# DP2MBPR_1_0.net
KiCad netlist of a schematic drawn in EAGLE
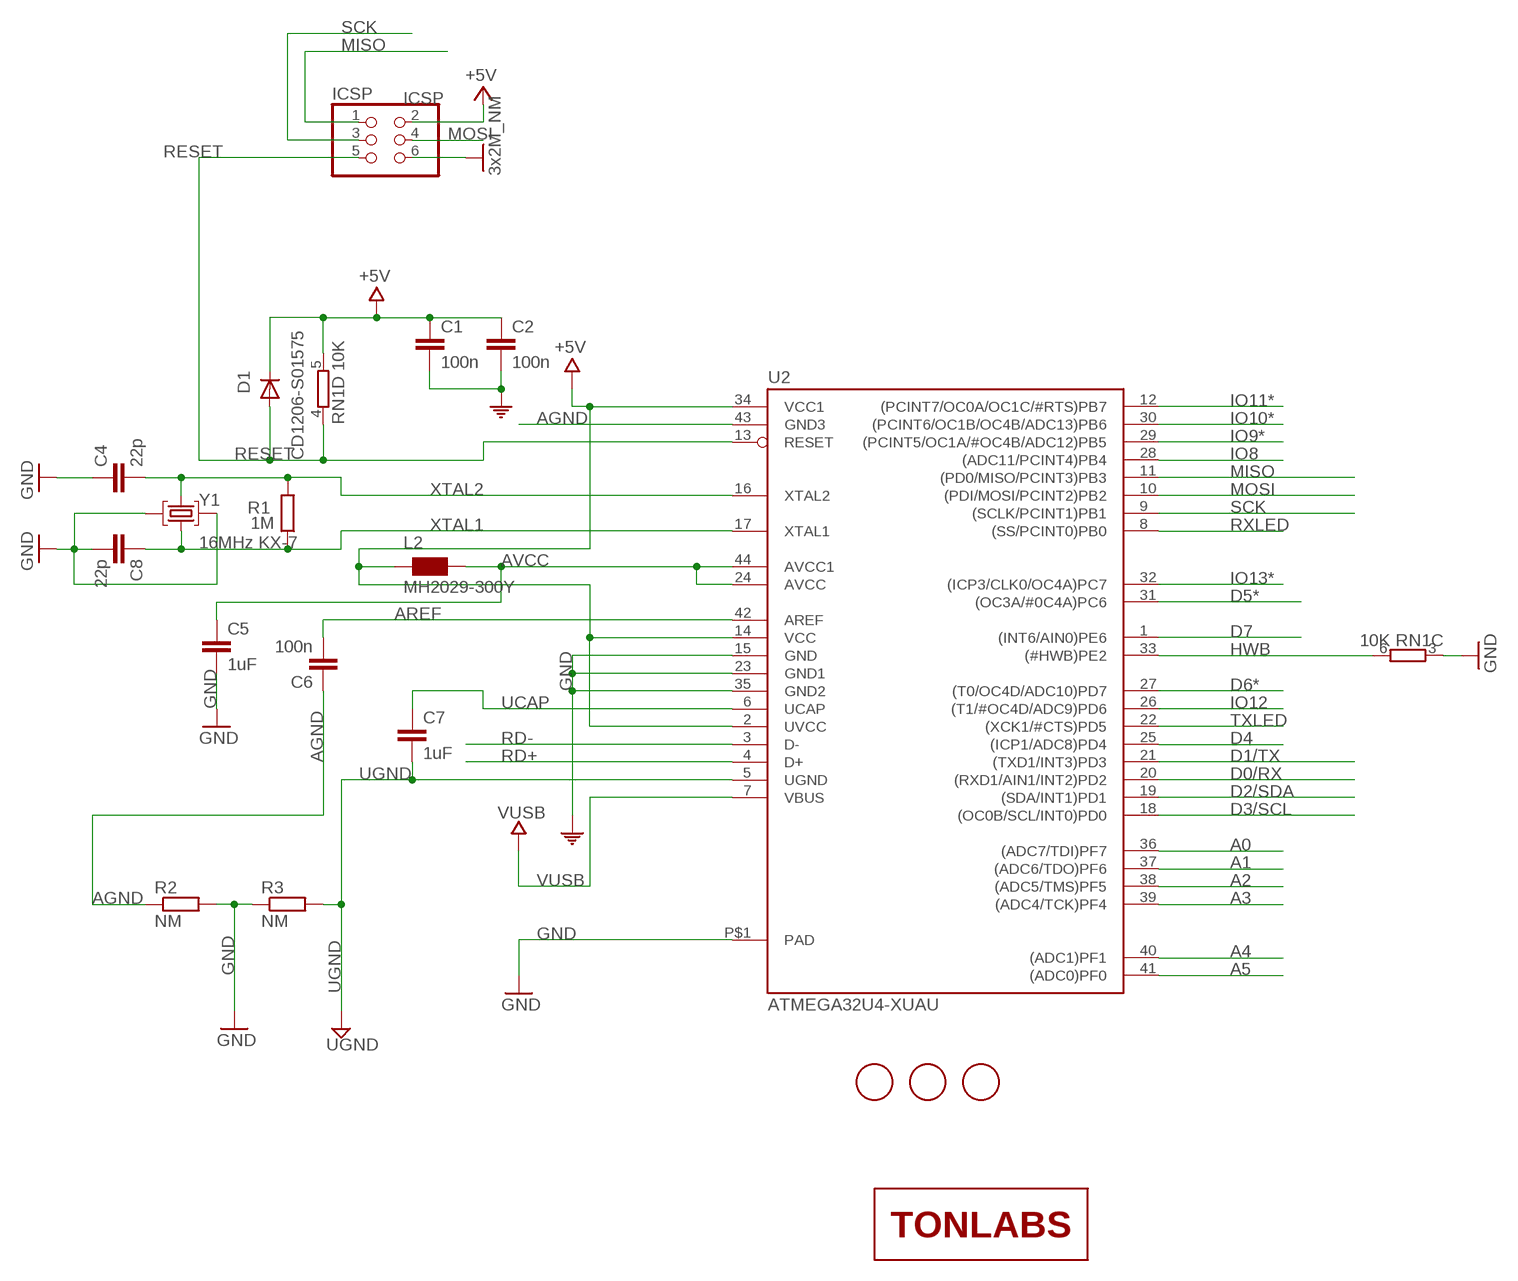
[diagram p0: schematic, sheet 2]
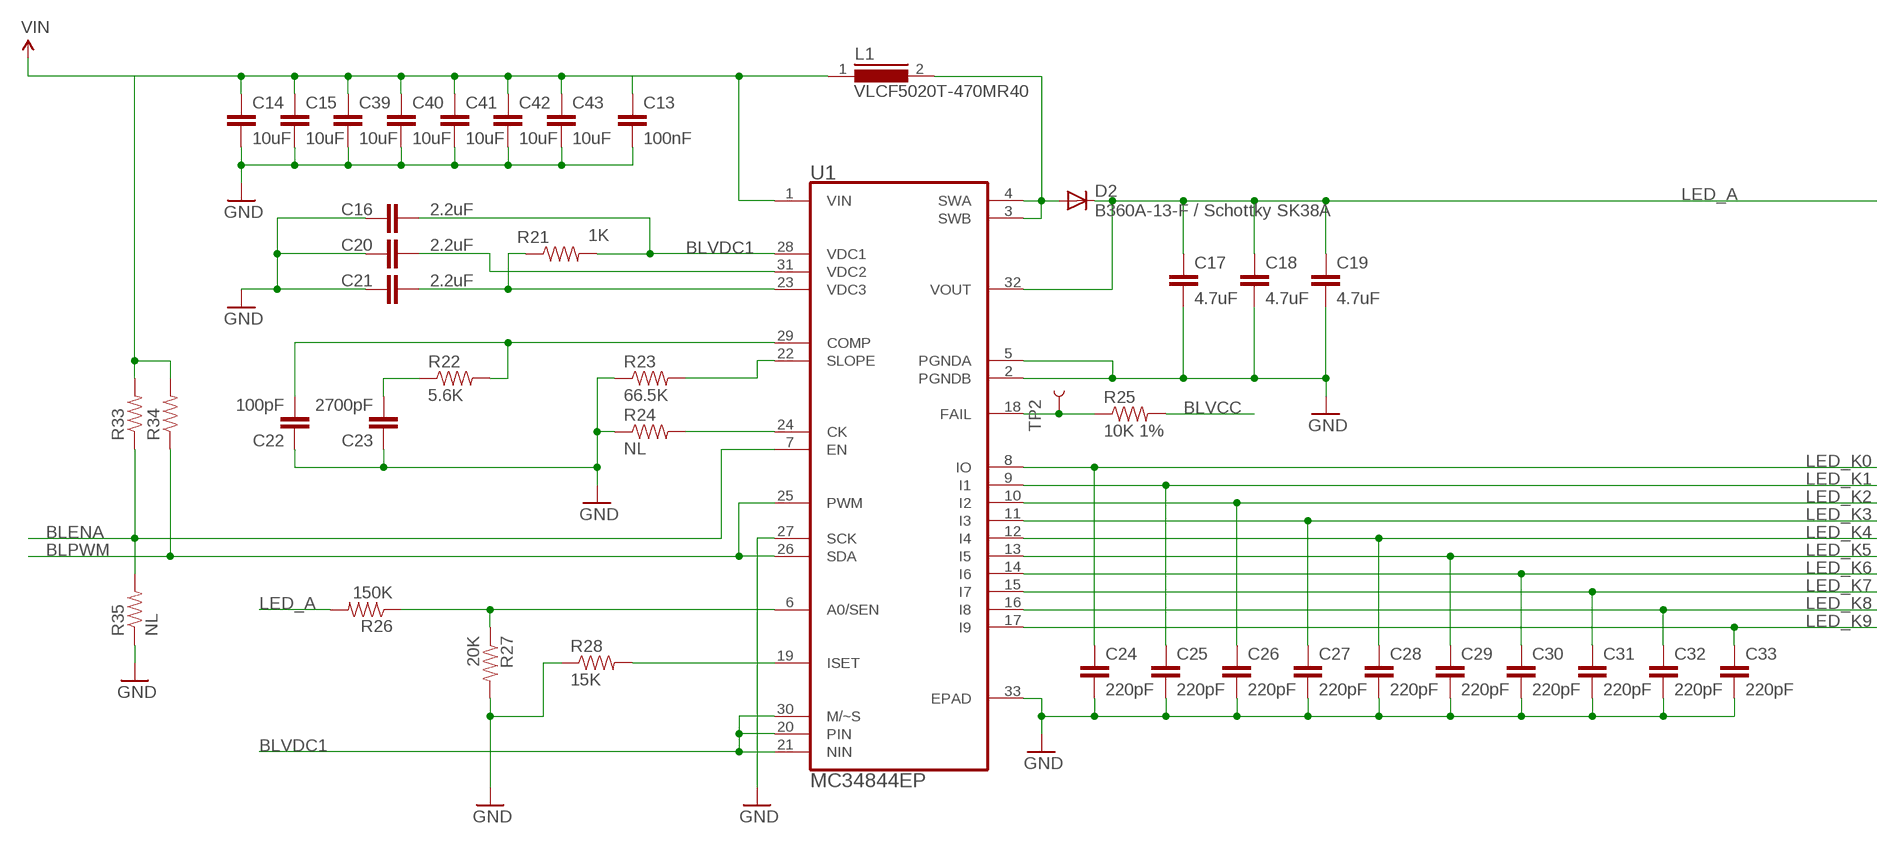
[diagram p1: schematic, sheet 3]
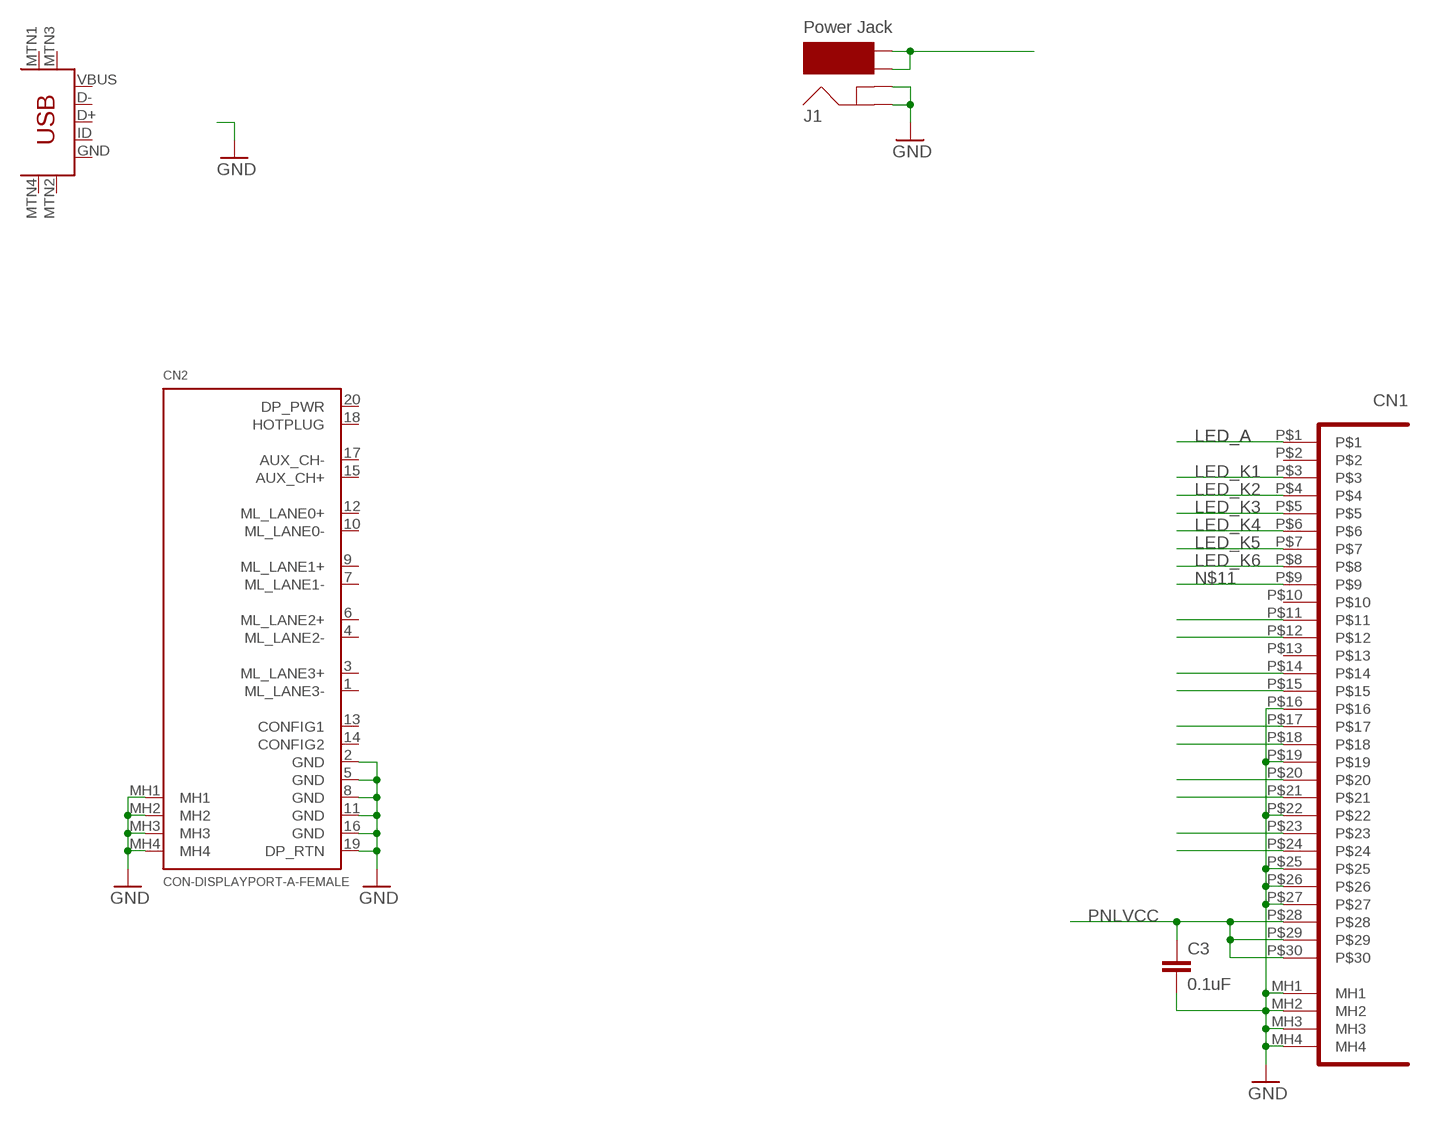
[diagram p2: schematic, sheet 4]

(export (version "E")
  (design (tool "Eeschema 10.0.6"))
  (components
    (comp (ref "C1")
      (value "100n")
      (footprint "eagle-import:C0603-ROUND")
      (libsource (lib "eagle-import") (part "C-EUC0603"))
    )
    (comp (ref "C2")
      (value "100n")
      (footprint "eagle-import:C0603-ROUND")
      (libsource (lib "eagle-import") (part "C-EUC0603"))
    )
    (comp (ref "C4")
      (value "22p")
      (footprint "eagle-import:C0603-ROUND")
      (libsource (lib "eagle-import") (part "C-EUC0603"))
    )
    (comp (ref "C5")
      (value "1uF")
      (footprint "eagle-import:C0603-ROUND")
      (libsource (lib "eagle-import") (part "C-EUC0603"))
    )
    (comp (ref "C6")
      (value "100n")
      (footprint "eagle-import:C0603-ROUND")
      (libsource (lib "eagle-import") (part "C-EUC0603"))
    )
    (comp (ref "C7")
      (value "1uF")
      (footprint "eagle-import:C0603-ROUND")
      (libsource (lib "eagle-import") (part "C-EUC0603"))
    )
    (comp (ref "C8")
      (value "22p")
      (footprint "eagle-import:C0603-ROUND")
      (libsource (lib "eagle-import") (part "C-EUC0603"))
    )
    (comp (ref "D1")
      (value "CD1206-S01575")
      (footprint "eagle-import:MINIMELF")
      (libsource (lib "eagle-import") (part "DIODE-MINIMELF"))
    )
    (comp (ref "FID1")
      (value "FIDUCIALMOUNT")
      (footprint "eagle-import:FIDUCIA-MOUNT")
      (libsource (lib "eagle-import") (part "FIDUCIALMOUNT"))
    )
    (comp (ref "FID2")
      (value "FIDUCIALMOUNT")
      (footprint "eagle-import:FIDUCIA-MOUNT")
      (libsource (lib "eagle-import") (part "FIDUCIALMOUNT"))
    )
    (comp (ref "FID3")
      (value "FIDUCIALMOUNT")
      (footprint "eagle-import:FIDUCIA-MOUNT")
      (libsource (lib "eagle-import") (part "FIDUCIALMOUNT"))
    )
    (comp (ref "ICSP")
      (value "ICSP")
      (footprint "eagle-import:2X03")
      (libsource (lib "eagle-import") (part "PINHD-2X3"))
    )
    (comp (ref "L2")
      (value "MH2029-300Y")
      (footprint "eagle-import:0805")
      (libsource (lib "eagle-import") (part "WE-CBF_0805"))
    )
    (comp (ref "LOGO1")
      (value "LOGO-TONYLABSMED-LANDSCAPE")
      (footprint "eagle-import:LOGO-TONYLABS-MED-LANDSCAPE")
      (libsource (lib "eagle-import") (part "LOGO-TONYLABSMED-LANDSCAPE"))
    )
    (comp (ref "R1")
      (value "1M")
      (footprint "eagle-import:R0603-ROUND")
      (libsource (lib "eagle-import") (part "R-EU_R0603"))
    )
    (comp (ref "R2")
      (value "NM")
      (footprint "eagle-import:R0402")
      (libsource (lib "eagle-import") (part "R-EU_R0402"))
    )
    (comp (ref "R3")
      (value "NM")
      (footprint "eagle-import:R0402")
      (libsource (lib "eagle-import") (part "R-EU_R0402"))
    )
    (comp (ref "RN1")
      (value "10K")
      (footprint "eagle-import:CAY16")
      (libsource (lib "eagle-import") (part "4R-NCAY16"))
    )
    (comp (ref "U2")
      (value "ATMEGA32U4-XUAU")
      (footprint "eagle-import:TQFP44-PAD")
      (libsource (lib "eagle-import") (part "ATMEGA32U4-XUAU"))
    )
    (comp (ref "Y1")
      (value "16MHz KX-7")
      (footprint "eagle-import:CRYSTAL-3.2-2.5")
      (libsource (lib "eagle-import") (part "CRYSTAL-3.2-2.5"))
    )
    (comp (ref "C13")
      (value "100nF")
      (footprint "eagle-import:0805")
      (libsource (lib "eagle-import") (part "CAP0805"))
    )
    (comp (ref "C14")
      (value "10uF")
      (footprint "eagle-import:0805")
      (libsource (lib "eagle-import") (part "CAP0805"))
    )
    (comp (ref "C15")
      (value "10uF")
      (footprint "eagle-import:0805")
      (libsource (lib "eagle-import") (part "CAP0805"))
    )
    (comp (ref "C16")
      (value "2.2uF")
      (footprint "eagle-import:0805")
      (libsource (lib "eagle-import") (part "CAP0805"))
    )
    (comp (ref "C17")
      (value "4.7uF")
      (footprint "eagle-import:1210")
      (libsource (lib "eagle-import") (part "CAP1210"))
    )
    (comp (ref "C18")
      (value "4.7uF")
      (footprint "eagle-import:1210")
      (libsource (lib "eagle-import") (part "CAP1210"))
    )
    (comp (ref "C19")
      (value "4.7uF")
      (footprint "eagle-import:1210")
      (libsource (lib "eagle-import") (part "CAP1210"))
    )
    (comp (ref "C20")
      (value "2.2uF")
      (footprint "eagle-import:0805")
      (libsource (lib "eagle-import") (part "CAP0805"))
    )
    (comp (ref "C21")
      (value "2.2uF")
      (footprint "eagle-import:0805")
      (libsource (lib "eagle-import") (part "CAP0805"))
    )
    (comp (ref "C22")
      (value "100pF")
      (footprint "eagle-import:0805")
      (libsource (lib "eagle-import") (part "CAP0805"))
    )
    (comp (ref "C23")
      (value "2700pF")
      (footprint "eagle-import:0805")
      (libsource (lib "eagle-import") (part "CAP0805"))
    )
    (comp (ref "C24")
      (value "220pF")
      (footprint "eagle-import:0603-CAP")
      (libsource (lib "eagle-import") (part "CAP0603-CAP"))
    )
    (comp (ref "C25")
      (value "220pF")
      (footprint "eagle-import:0603-CAP")
      (libsource (lib "eagle-import") (part "CAP0603-CAP"))
    )
    (comp (ref "C26")
      (value "220pF")
      (footprint "eagle-import:0603-CAP")
      (libsource (lib "eagle-import") (part "CAP0603-CAP"))
    )
    (comp (ref "C27")
      (value "220pF")
      (footprint "eagle-import:0603-CAP")
      (libsource (lib "eagle-import") (part "CAP0603-CAP"))
    )
    (comp (ref "C28")
      (value "220pF")
      (footprint "eagle-import:0603-CAP")
      (libsource (lib "eagle-import") (part "CAP0603-CAP"))
    )
    (comp (ref "C29")
      (value "220pF")
      (footprint "eagle-import:0603-CAP")
      (libsource (lib "eagle-import") (part "CAP0603-CAP"))
    )
    (comp (ref "C30")
      (value "220pF")
      (footprint "eagle-import:0603-CAP")
      (libsource (lib "eagle-import") (part "CAP0603-CAP"))
    )
    (comp (ref "C31")
      (value "220pF")
      (footprint "eagle-import:0603-CAP")
      (libsource (lib "eagle-import") (part "CAP0603-CAP"))
    )
    (comp (ref "C32")
      (value "220pF")
      (footprint "eagle-import:0603-CAP")
      (libsource (lib "eagle-import") (part "CAP0603-CAP"))
    )
    (comp (ref "C33")
      (value "220pF")
      (footprint "eagle-import:0603-CAP")
      (libsource (lib "eagle-import") (part "CAP0603-CAP"))
    )
    (comp (ref "C39")
      (value "10uF")
      (footprint "eagle-import:0805")
      (libsource (lib "eagle-import") (part "CAP0805"))
    )
    (comp (ref "C40")
      (value "10uF")
      (footprint "eagle-import:0805")
      (libsource (lib "eagle-import") (part "CAP0805"))
    )
    (comp (ref "C41")
      (value "10uF")
      (footprint "eagle-import:0805")
      (libsource (lib "eagle-import") (part "CAP0805"))
    )
    (comp (ref "C42")
      (value "10uF")
      (footprint "eagle-import:0805")
      (libsource (lib "eagle-import") (part "CAP0805"))
    )
    (comp (ref "C43")
      (value "10uF")
      (footprint "eagle-import:0805")
      (libsource (lib "eagle-import") (part "CAP0805"))
    )
    (comp (ref "D2")
      (value "B360A-13-F / Schottky SK38A")
      (footprint "eagle-import:SMB")
      (libsource (lib "eagle-import") (part "DIODE-SMB"))
    )
    (comp (ref "L1")
      (value "VLCF5020T-470MR40")
      (footprint "eagle-import:SLF7045")
      (libsource (lib "eagle-import") (part "SLF7045"))
    )
    (comp (ref "R21")
      (value "1K")
      (footprint "eagle-import:0603-RES")
      (libsource (lib "eagle-import") (part "RESISTOR0603-RES"))
    )
    (comp (ref "R22")
      (value "5.6K")
      (footprint "eagle-import:0603-RES")
      (libsource (lib "eagle-import") (part "RESISTOR0603-RES"))
    )
    (comp (ref "R23")
      (value "66.5K")
      (footprint "eagle-import:0603-RES")
      (libsource (lib "eagle-import") (part "RESISTOR0603-RES"))
    )
    (comp (ref "R24")
      (value "NL")
      (footprint "eagle-import:0603-RES")
      (libsource (lib "eagle-import") (part "RESISTOR0603-RES"))
    )
    (comp (ref "R25")
      (value "10K 1%")
      (footprint "eagle-import:0603-RES")
      (libsource (lib "eagle-import") (part "RESISTOR0603-RES"))
    )
    (comp (ref "R26")
      (value "150K")
      (footprint "eagle-import:0603-RES")
      (libsource (lib "eagle-import") (part "RESISTOR0603-RES"))
    )
    (comp (ref "R27")
      (value "20K")
      (footprint "eagle-import:0603-RES")
      (libsource (lib "eagle-import") (part "RESISTOR0603-RES"))
    )
    (comp (ref "R28")
      (value "15K")
      (footprint "eagle-import:0603-RES")
      (libsource (lib "eagle-import") (part "RESISTOR0603-RES"))
    )
    (comp (ref "R33")
      (value "RESISTOR0603-RES")
      (footprint "eagle-import:0603-RES")
      (libsource (lib "eagle-import") (part "RESISTOR0603-RES"))
    )
    (comp (ref "R34")
      (value "RESISTOR0603-RES")
      (footprint "eagle-import:0603-RES")
      (libsource (lib "eagle-import") (part "RESISTOR0603-RES"))
    )
    (comp (ref "R35")
      (value "NL")
      (footprint "eagle-import:0603-RES")
      (libsource (lib "eagle-import") (part "RESISTOR0603-RES"))
    )
    (comp (ref "TP2")
      (value "TEST-POINT3X5")
      (footprint "eagle-import:PAD.03X.05")
      (libsource (lib "eagle-import") (part "TEST-POINT3X5"))
    )
    (comp (ref "U1")
      (value "MC34844EP")
      (footprint "eagle-import:QFN50P500X500X100-33N")
      (libsource (lib "eagle-import") (part "IC-FREESCALE-MC34844EP"))
    )
    (comp (ref "C3")
      (value "0.1uF")
      (footprint "eagle-import:0603-CAP")
      (libsource (lib "eagle-import") (part "CAP0603-CAP"))
    )
    (comp (ref "CN1")
      (value "CON-I_PEX-20474-030E")
      (footprint "eagle-import:CON-I_PEX-20474-030E-0.4PITCH_30PIN-SMT")
      (libsource (lib "eagle-import") (part "CON-I_PEX-20474-030E"))
    )
    (comp (ref "CN2")
      (value "CON-DISPLAYPORT-A-FEMALE")
      (footprint "eagle-import:CON-DISPLAYPORT-FEMALE-SMT")
      (libsource (lib "eagle-import") (part "CON-DISPLAYPORT-A-FEMALE"))
    )
    (comp (ref "J1")
      (value "Power Jack")
      (footprint "eagle-import:CON-POWER-JACK-4P")
      (libsource (lib "eagle-import") (part "CON-POWER-JACK-4P"))
    )
    (comp (ref "U$1")
      (value "USB-MINIB-5PIN")
      (footprint "eagle-import:USB-MINIB")
      (libsource (lib "eagle-import") (part "USB-MINIB-5PIN"))
    )
  )
  (nets
    (net (code "1") (name "+5V") (class "Default")
      (node (ref "C1") (pin "1") (pinfunction "1_1") (pintype "passive"))
      (node (ref "C2") (pin "1") (pinfunction "1_1") (pintype "passive"))
      (node (ref "D1") (pin "C") (pinfunction "C_C") (pintype "passive"))
      (node (ref "ICSP") (pin "2") (pinfunction "2_2") (pintype "passive"))
      (node (ref "L2") (pin "1") (pinfunction "1_1") (pintype "passive"))
      (node (ref "RN1") (pin "5") (pinfunction "2_5") (pintype "passive"))
      (node (ref "U2") (pin "14") (pinfunction "VCC_14") (pintype "power_in"))
      (node (ref "U2") (pin "2") (pinfunction "UVCC_2") (pintype "power_in"))
      (node (ref "U2") (pin "34") (pinfunction "VCC1_34") (pintype "power_in"))
    )
    (net (code "2") (name "A0") (class "Default")
      (node (ref "U2") (pin "36") (pinfunction "(ADC7/TDI)PF7_36") (pintype "bidirectional"))
    )
    (net (code "3") (name "A1") (class "Default")
      (node (ref "U2") (pin "37") (pinfunction "(ADC6/TDO)PF6_37") (pintype "bidirectional"))
    )
    (net (code "4") (name "A2") (class "Default")
      (node (ref "U2") (pin "38") (pinfunction "(ADC5/TMS)PF5_38") (pintype "bidirectional"))
    )
    (net (code "5") (name "A3") (class "Default")
      (node (ref "U2") (pin "39") (pinfunction "(ADC4/TCK)PF4_39") (pintype "bidirectional"))
    )
    (net (code "6") (name "A4") (class "Default")
      (node (ref "U2") (pin "40") (pinfunction "(ADC1)PF1_40") (pintype "bidirectional"))
    )
    (net (code "7") (name "A5") (class "Default")
      (node (ref "U2") (pin "41") (pinfunction "(ADC0)PF0_41") (pintype "bidirectional"))
    )
    (net (code "8") (name "AGND") (class "Default")
      (node (ref "C6") (pin "1") (pinfunction "1_1") (pintype "passive"))
      (node (ref "R2") (pin "1") (pinfunction "1_1") (pintype "passive"))
      (node (ref "U2") (pin "43") (pinfunction "GND3_43") (pintype "power_in"))
    )
    (net (code "9") (name "AREF") (class "Default")
      (node (ref "C6") (pin "2") (pinfunction "2_2") (pintype "passive"))
      (node (ref "U2") (pin "42") (pinfunction "AREF_42") (pintype "power_in"))
    )
    (net (code "10") (name "AVCC") (class "Default")
      (node (ref "C5") (pin "1") (pinfunction "1_1") (pintype "passive"))
      (node (ref "L2") (pin "2") (pinfunction "2_2") (pintype "passive"))
      (node (ref "U2") (pin "24") (pinfunction "AVCC_24") (pintype "power_in"))
      (node (ref "U2") (pin "44") (pinfunction "AVCC1_44") (pintype "power_in"))
    )
    (net (code "11") (name "BLENA") (class "Default")
      (node (ref "R33") (pin "1") (pinfunction "1_1") (pintype "passive"))
      (node (ref "R35") (pin "2") (pinfunction "2_2") (pintype "passive"))
      (node (ref "U1") (pin "7") (pinfunction "EN_7") (pintype "input"))
    )
    (net (code "12") (name "BLPWM") (class "Default")
      (node (ref "R34") (pin "1") (pinfunction "1_1") (pintype "passive"))
      (node (ref "U1") (pin "25") (pinfunction "PWM_25") (pintype "input"))
      (node (ref "U1") (pin "26") (pinfunction "SDA_26") (pintype "bidirectional"))
    )
    (net (code "13") (name "BLVCC") (class "Default")
      (node (ref "R25") (pin "2") (pinfunction "2_2") (pintype "passive"))
    )
    (net (code "14") (name "BLVDC1") (class "Default")
      (node (ref "C16") (pin "2") (pinfunction "2_2") (pintype "passive"))
      (node (ref "R21") (pin "2") (pinfunction "2_2") (pintype "passive"))
      (node (ref "U1") (pin "20") (pinfunction "PIN_20") (pintype "input"))
      (node (ref "U1") (pin "21") (pinfunction "NIN_21") (pintype "input"))
      (node (ref "U1") (pin "28") (pinfunction "VDC1_28") (pintype "output"))
      (node (ref "U1") (pin "30") (pinfunction "M/~{S}_30") (pintype "passive"))
    )
    (net (code "15") (name "D0{slash}RX") (class "Default")
      (node (ref "U2") (pin "20") (pinfunction "(RXD1/AIN1/INT2)PD2_20") (pintype "bidirectional"))
    )
    (net (code "16") (name "D1{slash}TX") (class "Default")
      (node (ref "U2") (pin "21") (pinfunction "(TXD1/INT3)PD3_21") (pintype "bidirectional"))
    )
    (net (code "17") (name "D2{slash}SDA") (class "Default")
      (node (ref "U2") (pin "19") (pinfunction "(SDA/INT1)PD1_19") (pintype "bidirectional"))
    )
    (net (code "18") (name "D3{slash}SCL") (class "Default")
      (node (ref "U2") (pin "18") (pinfunction "(OC0B/SCL/INT0)PD0_18") (pintype "bidirectional"))
    )
    (net (code "19") (name "D4") (class "Default")
      (node (ref "U2") (pin "25") (pinfunction "(ICP1/ADC8)PD4_25") (pintype "bidirectional"))
    )
    (net (code "20") (name "D5*") (class "Default")
      (node (ref "U2") (pin "31") (pinfunction "(OC3A/#0C4A)PC6_31") (pintype "bidirectional"))
    )
    (net (code "21") (name "D6*") (class "Default")
      (node (ref "U2") (pin "27") (pinfunction "(T0/OC4D/ADC10)PD7_27") (pintype "bidirectional"))
    )
    (net (code "22") (name "D7") (class "Default")
      (node (ref "U2") (pin "1") (pinfunction "(INT6/AIN0)PE6_1") (pintype "bidirectional"))
    )
    (net (code "23") (name "GND") (class "Default")
      (node (ref "C1") (pin "2") (pinfunction "2_2") (pintype "passive"))
      (node (ref "C13") (pin "2") (pinfunction "2_2") (pintype "passive"))
      (node (ref "C14") (pin "2") (pinfunction "2_2") (pintype "passive"))
      (node (ref "C15") (pin "2") (pinfunction "2_2") (pintype "passive"))
      (node (ref "C16") (pin "1") (pinfunction "1_1") (pintype "passive"))
      (node (ref "C17") (pin "2") (pinfunction "2_2") (pintype "passive"))
      (node (ref "C18") (pin "2") (pinfunction "2_2") (pintype "passive"))
      (node (ref "C19") (pin "2") (pinfunction "2_2") (pintype "passive"))
      (node (ref "C2") (pin "2") (pinfunction "2_2") (pintype "passive"))
      (node (ref "C20") (pin "1") (pinfunction "1_1") (pintype "passive"))
      (node (ref "C21") (pin "1") (pinfunction "1_1") (pintype "passive"))
      (node (ref "C22") (pin "1") (pinfunction "1_1") (pintype "passive"))
      (node (ref "C23") (pin "1") (pinfunction "1_1") (pintype "passive"))
      (node (ref "C24") (pin "2") (pinfunction "2_2") (pintype "passive"))
      (node (ref "C25") (pin "2") (pinfunction "2_2") (pintype "passive"))
      (node (ref "C26") (pin "2") (pinfunction "2_2") (pintype "passive"))
      (node (ref "C27") (pin "2") (pinfunction "2_2") (pintype "passive"))
      (node (ref "C28") (pin "2") (pinfunction "2_2") (pintype "passive"))
      (node (ref "C29") (pin "2") (pinfunction "2_2") (pintype "passive"))
      (node (ref "C3") (pin "2") (pinfunction "2_2") (pintype "passive"))
      (node (ref "C30") (pin "2") (pinfunction "2_2") (pintype "passive"))
      (node (ref "C31") (pin "2") (pinfunction "2_2") (pintype "passive"))
      (node (ref "C32") (pin "2") (pinfunction "2_2") (pintype "passive"))
      (node (ref "C33") (pin "2") (pinfunction "2_2") (pintype "passive"))
      (node (ref "C39") (pin "2") (pinfunction "2_2") (pintype "passive"))
      (node (ref "C4") (pin "1") (pinfunction "1_1") (pintype "passive"))
      (node (ref "C40") (pin "2") (pinfunction "2_2") (pintype "passive"))
      (node (ref "C41") (pin "2") (pinfunction "2_2") (pintype "passive"))
      (node (ref "C42") (pin "2") (pinfunction "2_2") (pintype "passive"))
      (node (ref "C43") (pin "2") (pinfunction "2_2") (pintype "passive"))
      (node (ref "C5") (pin "2") (pinfunction "2_2") (pintype "passive"))
      (node (ref "C8") (pin "2") (pinfunction "2_2") (pintype "passive"))
      (node (ref "CN1") (pin "MH1") (pinfunction "MH1_MH1") (pintype "bidirectional"))
      (node (ref "CN1") (pin "MH2") (pinfunction "MH2_MH2") (pintype "bidirectional"))
      (node (ref "CN1") (pin "MH3") (pinfunction "MH3_MH3") (pintype "bidirectional"))
      (node (ref "CN1") (pin "MH4") (pinfunction "MH4_MH4") (pintype "bidirectional"))
      (node (ref "CN1") (pin "P$16") (pinfunction "P$16_P$16") (pintype "bidirectional"))
      (node (ref "CN1") (pin "P$19") (pinfunction "P$19_P$19") (pintype "bidirectional"))
      (node (ref "CN1") (pin "P$22") (pinfunction "P$22_P$22") (pintype "bidirectional"))
      (node (ref "CN1") (pin "P$25") (pinfunction "P$25_P$25") (pintype "bidirectional"))
      (node (ref "CN1") (pin "P$26") (pinfunction "P$26_P$26") (pintype "bidirectional"))
      (node (ref "CN1") (pin "P$27") (pinfunction "P$27_P$27") (pintype "bidirectional"))
      (node (ref "CN2") (pin "11") (pinfunction "GND_11") (pintype "bidirectional"))
      (node (ref "CN2") (pin "16") (pinfunction "GND_16") (pintype "bidirectional"))
      (node (ref "CN2") (pin "19") (pinfunction "DP_RTN_19") (pintype "bidirectional"))
      (node (ref "CN2") (pin "2") (pinfunction "GND_2") (pintype "bidirectional"))
      (node (ref "CN2") (pin "5") (pinfunction "GND_5") (pintype "bidirectional"))
      (node (ref "CN2") (pin "8") (pinfunction "GND_8") (pintype "bidirectional"))
      (node (ref "CN2") (pin "MH1") (pinfunction "MH1_MH1") (pintype "bidirectional"))
      (node (ref "CN2") (pin "MH2") (pinfunction "MH2_MH2") (pintype "bidirectional"))
      (node (ref "CN2") (pin "MH3") (pinfunction "MH3_MH3") (pintype "bidirectional"))
      (node (ref "CN2") (pin "MH4") (pinfunction "MH4_MH4") (pintype "bidirectional"))
      (node (ref "ICSP") (pin "6") (pinfunction "6_6") (pintype "passive"))
      (node (ref "J1") (pin "GND") (pinfunction "GND_GND") (pintype "bidirectional"))
      (node (ref "J1") (pin "P$4") (pinfunction "GNDBREAK_P$4") (pintype "bidirectional"))
      (node (ref "R2") (pin "2") (pinfunction "2_2") (pintype "passive"))
      (node (ref "R23") (pin "1") (pinfunction "1_1") (pintype "passive"))
      (node (ref "R24") (pin "1") (pinfunction "1_1") (pintype "passive"))
      (node (ref "R27") (pin "2") (pinfunction "2_2") (pintype "passive"))
      (node (ref "R28") (pin "1") (pinfunction "1_1") (pintype "passive"))
      (node (ref "R3") (pin "1") (pinfunction "1_1") (pintype "passive"))
      (node (ref "R35") (pin "1") (pinfunction "1_1") (pintype "passive"))
      (node (ref "RN1") (pin "3") (pinfunction "1_3") (pintype "passive"))
      (node (ref "U1") (pin "2") (pinfunction "PGNDB_2") (pintype "passive"))
      (node (ref "U1") (pin "27") (pinfunction "SCK_27") (pintype "input"))
      (node (ref "U1") (pin "33") (pinfunction "EPAD_33") (pintype "passive"))
      (node (ref "U1") (pin "5") (pinfunction "PGNDA_5") (pintype "passive"))
      (node (ref "U2") (pin "15") (pinfunction "GND_15") (pintype "power_in"))
      (node (ref "U2") (pin "23") (pinfunction "GND1_23") (pintype "power_in"))
      (node (ref "U2") (pin "35") (pinfunction "GND2_35") (pintype "power_in"))
      (node (ref "U2") (pin "P$1") (pinfunction "PAD_P$1") (pintype "power_in"))
      (node (ref "Y1") (pin "2") (pinfunction "GND_2") (pintype "passive"))
      (node (ref "Y1") (pin "4") (pinfunction "GND_4") (pintype "passive"))
    )
    (net (code "24") (name "HWB") (class "Default")
      (node (ref "RN1") (pin "6") (pinfunction "2_6") (pintype "passive"))
      (node (ref "U2") (pin "33") (pinfunction "(#HWB)PE2_33") (pintype "bidirectional"))
    )
    (net (code "25") (name "IO8") (class "Default")
      (node (ref "U2") (pin "28") (pinfunction "(ADC11/PCINT4)PB4_28") (pintype "bidirectional"))
    )
    (net (code "26") (name "IO9*") (class "Default")
      (node (ref "U2") (pin "29") (pinfunction "(PCINT5/OC1A/#OC4B/ADC12)PB5_29") (pintype "bidirectional"))
    )
    (net (code "27") (name "IO10*") (class "Default")
      (node (ref "U2") (pin "30") (pinfunction "(PCINT6/OC1B/OC4B/ADC13)PB6_30") (pintype "bidirectional"))
    )
    (net (code "28") (name "IO11*") (class "Default")
      (node (ref "U2") (pin "12") (pinfunction "(PCINT7/OC0A/OC1C/#RTS)PB7_12") (pintype "bidirectional"))
    )
    (net (code "29") (name "IO12") (class "Default")
      (node (ref "U2") (pin "26") (pinfunction "(T1/#OC4D/ADC9)PD6_26") (pintype "bidirectional"))
    )
    (net (code "30") (name "IO13*") (class "Default")
      (node (ref "U2") (pin "32") (pinfunction "(ICP3/CLK0/OC4A)PC7_32") (pintype "bidirectional"))
    )
    (net (code "31") (name "LED_A") (class "Default")
      (node (ref "C17") (pin "1") (pinfunction "1_1") (pintype "passive"))
      (node (ref "C18") (pin "1") (pinfunction "1_1") (pintype "passive"))
      (node (ref "C19") (pin "1") (pinfunction "1_1") (pintype "passive"))
      (node (ref "CN1") (pin "P$1") (pinfunction "P$1_P$1") (pintype "bidirectional"))
      (node (ref "D2") (pin "C") (pinfunction "C_C") (pintype "passive"))
      (node (ref "R26") (pin "2") (pinfunction "2_2") (pintype "passive"))
      (node (ref "U1") (pin "32") (pinfunction "VOUT_32") (pintype "output"))
    )
    (net (code "32") (name "LED_K0") (class "Default")
      (node (ref "C24") (pin "1") (pinfunction "1_1") (pintype "passive"))
      (node (ref "U1") (pin "8") (pinfunction "IO_8") (pintype "input"))
    )
    (net (code "33") (name "LED_K1") (class "Default")
      (node (ref "C25") (pin "1") (pinfunction "1_1") (pintype "passive"))
      (node (ref "CN1") (pin "P$3") (pinfunction "P$3_P$3") (pintype "bidirectional"))
      (node (ref "U1") (pin "9") (pinfunction "I1_9") (pintype "input"))
    )
    (net (code "34") (name "LED_K2") (class "Default")
      (node (ref "C26") (pin "1") (pinfunction "1_1") (pintype "passive"))
      (node (ref "CN1") (pin "P$4") (pinfunction "P$4_P$4") (pintype "bidirectional"))
      (node (ref "U1") (pin "10") (pinfunction "I2_10") (pintype "input"))
    )
    (net (code "35") (name "LED_K3") (class "Default")
      (node (ref "C27") (pin "1") (pinfunction "1_1") (pintype "passive"))
      (node (ref "CN1") (pin "P$5") (pinfunction "P$5_P$5") (pintype "bidirectional"))
      (node (ref "U1") (pin "11") (pinfunction "I3_11") (pintype "input"))
    )
    (net (code "36") (name "LED_K4") (class "Default")
      (node (ref "C28") (pin "1") (pinfunction "1_1") (pintype "passive"))
      (node (ref "CN1") (pin "P$6") (pinfunction "P$6_P$6") (pintype "bidirectional"))
      (node (ref "U1") (pin "12") (pinfunction "I4_12") (pintype "input"))
    )
    (net (code "37") (name "LED_K5") (class "Default")
      (node (ref "C29") (pin "1") (pinfunction "1_1") (pintype "passive"))
      (node (ref "CN1") (pin "P$7") (pinfunction "P$7_P$7") (pintype "bidirectional"))
      (node (ref "U1") (pin "13") (pinfunction "I5_13") (pintype "input"))
    )
    (net (code "38") (name "LED_K6") (class "Default")
      (node (ref "C30") (pin "1") (pinfunction "1_1") (pintype "passive"))
      (node (ref "CN1") (pin "P$8") (pinfunction "P$8_P$8") (pintype "bidirectional"))
      (node (ref "U1") (pin "14") (pinfunction "I6_14") (pintype "input"))
    )
    (net (code "39") (name "LED_K7") (class "Default")
      (node (ref "C31") (pin "1") (pinfunction "1_1") (pintype "passive"))
      (node (ref "U1") (pin "15") (pinfunction "I7_15") (pintype "input"))
    )
    (net (code "40") (name "LED_K8") (class "Default")
      (node (ref "C32") (pin "1") (pinfunction "1_1") (pintype "passive"))
      (node (ref "U1") (pin "16") (pinfunction "I8_16") (pintype "input"))
    )
    (net (code "41") (name "LED_K9") (class "Default")
      (node (ref "C33") (pin "1") (pinfunction "1_1") (pintype "passive"))
      (node (ref "U1") (pin "17") (pinfunction "I9_17") (pintype "input"))
    )
    (net (code "42") (name "MISO") (class "Default")
      (node (ref "ICSP") (pin "1") (pinfunction "1_1") (pintype "passive"))
      (node (ref "U2") (pin "11") (pinfunction "(PD0/MISO/PCINT3)PB3_11") (pintype "bidirectional"))
    )
    (net (code "43") (name "MOSI") (class "Default")
      (node (ref "ICSP") (pin "4") (pinfunction "4_4") (pintype "passive"))
      (node (ref "U2") (pin "10") (pinfunction "(PDI/MOSI/PCINT2)PB2_10") (pintype "bidirectional"))
    )
    (net (code "44") (name "N$11") (class "Default")
      (node (ref "CN1") (pin "P$9") (pinfunction "P$9_P$9") (pintype "bidirectional"))
    )
    (net (code "45") (name "Net-(C23-Pad2)") (class "Default")
      (node (ref "C23") (pin "2") (pinfunction "2_2") (pintype "passive"))
      (node (ref "R22") (pin "1") (pinfunction "1_1") (pintype "passive"))
    )
    (net (code "46") (name "Net-(J1-PWR)") (class "Default")
      (node (ref "J1") (pin "VIN0") (pinfunction "PWR_VIN0") (pintype "bidirectional"))
      (node (ref "J1") (pin "VIN1") (pinfunction "PWR1_VIN1") (pintype "bidirectional"))
    )
    (net (code "47") (name "Net-(TP2-1)") (class "Default")
      (node (ref "R25") (pin "1") (pinfunction "1_1") (pintype "passive"))
      (node (ref "TP2") (pin "P$1") (pinfunction "1_P$1") (pintype "bidirectional"))
      (node (ref "U1") (pin "18") (pinfunction "FAIL_18") (pintype "passive"))
    )
    (net (code "48") (name "Net-(U1-A0{slash}SEN)") (class "Default")
      (node (ref "R26") (pin "1") (pinfunction "1_1") (pintype "passive"))
      (node (ref "R27") (pin "1") (pinfunction "1_1") (pintype "passive"))
      (node (ref "U1") (pin "6") (pinfunction "A0/SEN_6") (pintype "input"))
    )
    (net (code "49") (name "Net-(U1-CK)") (class "Default")
      (node (ref "R24") (pin "2") (pinfunction "2_2") (pintype "passive"))
      (node (ref "U1") (pin "24") (pinfunction "CK_24") (pintype "input"))
    )
    (net (code "50") (name "Net-(U1-COMP)") (class "Default")
      (node (ref "C22") (pin "2") (pinfunction "2_2") (pintype "passive"))
      (node (ref "R22") (pin "2") (pinfunction "2_2") (pintype "passive"))
      (node (ref "U1") (pin "29") (pinfunction "COMP_29") (pintype "input"))
    )
    (net (code "51") (name "Net-(U1-ISET)") (class "Default")
      (node (ref "R28") (pin "2") (pinfunction "2_2") (pintype "passive"))
      (node (ref "U1") (pin "19") (pinfunction "ISET_19") (pintype "passive"))
    )
    (net (code "52") (name "Net-(U1-SLOPE)") (class "Default")
      (node (ref "R23") (pin "2") (pinfunction "2_2") (pintype "passive"))
      (node (ref "U1") (pin "22") (pinfunction "SLOPE_22") (pintype "passive"))
    )
    (net (code "53") (name "Net-(U1-SWA)") (class "Default")
      (node (ref "D2") (pin "A") (pinfunction "A_A") (pintype "passive"))
      (node (ref "L1") (pin "2") (pinfunction "2_2") (pintype "passive"))
      (node (ref "U1") (pin "3") (pinfunction "SWB_3") (pintype "input"))
      (node (ref "U1") (pin "4") (pinfunction "SWA_4") (pintype "input"))
    )
    (net (code "54") (name "Net-(U1-VDC2)") (class "Default")
      (node (ref "C20") (pin "2") (pinfunction "2_2") (pintype "passive"))
      (node (ref "U1") (pin "31") (pinfunction "VDC2_31") (pintype "output"))
    )
    (net (code "55") (name "Net-(U1-VDC3)") (class "Default")
      (node (ref "C21") (pin "2") (pinfunction "2_2") (pintype "passive"))
      (node (ref "R21") (pin "1") (pinfunction "1_1") (pintype "passive"))
      (node (ref "U1") (pin "23") (pinfunction "VDC3_23") (pintype "output"))
    )
    (net (code "56") (name "PNLVCC") (class "Default")
      (node (ref "C3") (pin "1") (pinfunction "1_1") (pintype "passive"))
      (node (ref "CN1") (pin "P$28") (pinfunction "P$28_P$28") (pintype "bidirectional"))
      (node (ref "CN1") (pin "P$29") (pinfunction "P$29_P$29") (pintype "bidirectional"))
      (node (ref "CN1") (pin "P$30") (pinfunction "P$30_P$30") (pintype "bidirectional"))
    )
    (net (code "57") (name "RD+") (class "Default")
      (node (ref "U2") (pin "4") (pinfunction "D+_4") (pintype "bidirectional"))
    )
    (net (code "58") (name "RD-") (class "Default")
      (node (ref "U2") (pin "3") (pinfunction "D-_3") (pintype "bidirectional"))
    )
    (net (code "59") (name "RESET") (class "Default")
      (node (ref "D1") (pin "A") (pinfunction "A_A") (pintype "passive"))
      (node (ref "ICSP") (pin "5") (pinfunction "5_5") (pintype "passive"))
      (node (ref "RN1") (pin "4") (pinfunction "1_4") (pintype "passive"))
      (node (ref "U2") (pin "13") (pinfunction "RESET_13") (pintype "input"))
    )
    (net (code "60") (name "RXLED") (class "Default")
      (node (ref "U2") (pin "8") (pinfunction "(SS/PCINT0)PB0_8") (pintype "bidirectional"))
    )
    (net (code "61") (name "SCK") (class "Default")
      (node (ref "ICSP") (pin "3") (pinfunction "3_3") (pintype "passive"))
      (node (ref "U2") (pin "9") (pinfunction "(SCLK/PCINT1)PB1_9") (pintype "bidirectional"))
    )
    (net (code "62") (name "TXLED") (class "Default")
      (node (ref "U2") (pin "22") (pinfunction "(XCK1/#CTS)PD5_22") (pintype "bidirectional"))
    )
    (net (code "63") (name "UCAP") (class "Default")
      (node (ref "C7") (pin "1") (pinfunction "1_1") (pintype "passive"))
      (node (ref "U2") (pin "6") (pinfunction "UCAP_6") (pintype "passive"))
    )
    (net (code "64") (name "UGND") (class "Default")
      (node (ref "C7") (pin "2") (pinfunction "2_2") (pintype "passive"))
      (node (ref "R3") (pin "2") (pinfunction "2_2") (pintype "passive"))
      (node (ref "U2") (pin "5") (pinfunction "UGND_5") (pintype "power_in"))
    )
    (net (code "65") (name "VIN") (class "Default")
      (node (ref "C13") (pin "1") (pinfunction "1_1") (pintype "passive"))
      (node (ref "C14") (pin "1") (pinfunction "1_1") (pintype "passive"))
      (node (ref "C15") (pin "1") (pinfunction "1_1") (pintype "passive"))
      (node (ref "C39") (pin "1") (pinfunction "1_1") (pintype "passive"))
      (node (ref "C40") (pin "1") (pinfunction "1_1") (pintype "passive"))
      (node (ref "C41") (pin "1") (pinfunction "1_1") (pintype "passive"))
      (node (ref "C42") (pin "1") (pinfunction "1_1") (pintype "passive"))
      (node (ref "C43") (pin "1") (pinfunction "1_1") (pintype "passive"))
      (node (ref "L1") (pin "1") (pinfunction "1_1") (pintype "passive"))
      (node (ref "R33") (pin "2") (pinfunction "2_2") (pintype "passive"))
      (node (ref "R34") (pin "2") (pinfunction "2_2") (pintype "passive"))
      (node (ref "U1") (pin "1") (pinfunction "VIN_1") (pintype "power_in"))
    )
    (net (code "66") (name "VUSB") (class "Default")
      (node (ref "U2") (pin "7") (pinfunction "VBUS_7") (pintype "input"))
    )
    (net (code "67") (name "XTAL1") (class "Default")
      (node (ref "C8") (pin "1") (pinfunction "1_1") (pintype "passive"))
      (node (ref "R1") (pin "1") (pinfunction "1_1") (pintype "passive"))
      (node (ref "U2") (pin "17") (pinfunction "XTAL1_17") (pintype "bidirectional"))
      (node (ref "Y1") (pin "1") (pinfunction "C1_1") (pintype "passive"))
    )
    (net (code "68") (name "XTAL2") (class "Default")
      (node (ref "C4") (pin "2") (pinfunction "2_2") (pintype "passive"))
      (node (ref "R1") (pin "2") (pinfunction "2_2") (pintype "passive"))
      (node (ref "U2") (pin "16") (pinfunction "XTAL2_16") (pintype "bidirectional"))
      (node (ref "Y1") (pin "3") (pinfunction "C2_3") (pintype "passive"))
    )
    (net (code "69") (name "unconnected-(CN1-PadP$2)") (class "Default")
      (node (ref "CN1") (pin "P$2") (pinfunction "P$2_P$2") (pintype "bidirectional"))
    )
    (net (code "70") (name "unconnected-(CN1-PadP$10)") (class "Default")
      (node (ref "CN1") (pin "P$10") (pinfunction "P$10_P$10") (pintype "bidirectional"))
    )
    (net (code "71") (name "unconnected-(CN1-PadP$11)") (class "Default")
      (node (ref "CN1") (pin "P$11") (pinfunction "P$11_P$11") (pintype "bidirectional"))
    )
    (net (code "72") (name "unconnected-(CN1-PadP$12)") (class "Default")
      (node (ref "CN1") (pin "P$12") (pinfunction "P$12_P$12") (pintype "bidirectional"))
    )
    (net (code "73") (name "unconnected-(CN1-PadP$13)") (class "Default")
      (node (ref "CN1") (pin "P$13") (pinfunction "P$13_P$13") (pintype "bidirectional"))
    )
    (net (code "74") (name "unconnected-(CN1-PadP$14)") (class "Default")
      (node (ref "CN1") (pin "P$14") (pinfunction "P$14_P$14") (pintype "bidirectional"))
    )
    (net (code "75") (name "unconnected-(CN1-PadP$15)") (class "Default")
      (node (ref "CN1") (pin "P$15") (pinfunction "P$15_P$15") (pintype "bidirectional"))
    )
    (net (code "76") (name "unconnected-(CN1-PadP$17)") (class "Default")
      (node (ref "CN1") (pin "P$17") (pinfunction "P$17_P$17") (pintype "bidirectional"))
    )
    (net (code "77") (name "unconnected-(CN1-PadP$18)") (class "Default")
      (node (ref "CN1") (pin "P$18") (pinfunction "P$18_P$18") (pintype "bidirectional"))
    )
    (net (code "78") (name "unconnected-(CN1-PadP$20)") (class "Default")
      (node (ref "CN1") (pin "P$20") (pinfunction "P$20_P$20") (pintype "bidirectional"))
    )
    (net (code "79") (name "unconnected-(CN1-PadP$21)") (class "Default")
      (node (ref "CN1") (pin "P$21") (pinfunction "P$21_P$21") (pintype "bidirectional"))
    )
    (net (code "80") (name "unconnected-(CN1-PadP$23)") (class "Default")
      (node (ref "CN1") (pin "P$23") (pinfunction "P$23_P$23") (pintype "bidirectional"))
    )
    (net (code "81") (name "unconnected-(CN1-PadP$24)") (class "Default")
      (node (ref "CN1") (pin "P$24") (pinfunction "P$24_P$24") (pintype "bidirectional"))
    )
    (net (code "82") (name "unconnected-(CN2-AUX_CH+-Pad15)") (class "Default")
      (node (ref "CN2") (pin "15") (pinfunction "AUX_CH+_15") (pintype "bidirectional"))
    )
    (net (code "83") (name "unconnected-(CN2-AUX_CH--Pad17)") (class "Default")
      (node (ref "CN2") (pin "17") (pinfunction "AUX_CH-_17") (pintype "bidirectional"))
    )
    (net (code "84") (name "unconnected-(CN2-CONFIG1-Pad13)") (class "Default")
      (node (ref "CN2") (pin "13") (pinfunction "CONFIG1_13") (pintype "no_connect"))
    )
    (net (code "85") (name "unconnected-(CN2-CONFIG2-Pad14)") (class "Default")
      (node (ref "CN2") (pin "14") (pinfunction "CONFIG2_14") (pintype "no_connect"))
    )
    (net (code "86") (name "unconnected-(CN2-DP_PWR-Pad20)") (class "Default")
      (node (ref "CN2") (pin "20") (pinfunction "DP_PWR_20") (pintype "bidirectional"))
    )
    (net (code "87") (name "unconnected-(CN2-HOTPLUG-Pad18)") (class "Default")
      (node (ref "CN2") (pin "18") (pinfunction "HOTPLUG_18") (pintype "bidirectional"))
    )
    (net (code "88") (name "unconnected-(CN2-ML_LANE0+-Pad12)") (class "Default")
      (node (ref "CN2") (pin "12") (pinfunction "ML_LANE0+_12") (pintype "bidirectional"))
    )
    (net (code "89") (name "unconnected-(CN2-ML_LANE0--Pad10)") (class "Default")
      (node (ref "CN2") (pin "10") (pinfunction "ML_LANE0-_10") (pintype "bidirectional"))
    )
    (net (code "90") (name "unconnected-(CN2-ML_LANE1+-Pad9)") (class "Default")
      (node (ref "CN2") (pin "9") (pinfunction "ML_LANE1+_9") (pintype "bidirectional"))
    )
    (net (code "91") (name "unconnected-(CN2-ML_LANE1--Pad7)") (class "Default")
      (node (ref "CN2") (pin "7") (pinfunction "ML_LANE1-_7") (pintype "bidirectional"))
    )
    (net (code "92") (name "unconnected-(CN2-ML_LANE2+-Pad6)") (class "Default")
      (node (ref "CN2") (pin "6") (pinfunction "ML_LANE2+_6") (pintype "bidirectional"))
    )
    (net (code "93") (name "unconnected-(CN2-ML_LANE2--Pad4)") (class "Default")
      (node (ref "CN2") (pin "4") (pinfunction "ML_LANE2-_4") (pintype "bidirectional"))
    )
    (net (code "94") (name "unconnected-(CN2-ML_LANE3+-Pad3)") (class "Default")
      (node (ref "CN2") (pin "3") (pinfunction "ML_LANE3+_3") (pintype "bidirectional"))
    )
    (net (code "95") (name "unconnected-(CN2-ML_LANE3--Pad1)") (class "Default")
      (node (ref "CN2") (pin "1") (pinfunction "ML_LANE3-_1") (pintype "bidirectional"))
    )
    (net (code "96") (name "unconnected-(U$1-MTN1-PadMTN3)") (class "Default")
      (node (ref "U$1") (pin "MTN3") (pinfunction "MTN1_MTN3") (pintype "bidirectional"))
    )
    (net (code "97") (name "unconnected-(U$1-MTN2-PadMTN1)") (class "Default")
      (node (ref "U$1") (pin "MTN1") (pinfunction "MTN2_MTN1") (pintype "bidirectional"))
    )
    (net (code "98") (name "unconnected-(U$1-MTN3-PadMTN2)") (class "Default")
      (node (ref "U$1") (pin "MTN2") (pinfunction "MTN3_MTN2") (pintype "bidirectional"))
    )
    (net (code "99") (name "unconnected-(U$1-PadD+)") (class "Default")
      (node (ref "U$1") (pin "D+") (pinfunction "D+_D+") (pintype "bidirectional"))
    )
    (net (code "100") (name "unconnected-(U$1-PadD-)") (class "Default")
      (node (ref "U$1") (pin "D-") (pinfunction "D-_D-") (pintype "bidirectional"))
    )
    (net (code "101") (name "unconnected-(U$1-PadGND)") (class "Default")
      (node (ref "U$1") (pin "GND") (pinfunction "GND_GND") (pintype "bidirectional"))
    )
    (net (code "102") (name "unconnected-(U$1-PadID)") (class "Default")
      (node (ref "U$1") (pin "ID") (pinfunction "ID_ID") (pintype "bidirectional"))
    )
    (net (code "103") (name "unconnected-(U$1-PadMTN4)") (class "Default")
      (node (ref "U$1") (pin "MTN4") (pinfunction "MTN4_MTN4") (pintype "bidirectional"))
    )
    (net (code "104") (name "unconnected-(U$1-PadVBUS)") (class "Default")
      (node (ref "U$1") (pin "VBUS") (pinfunction "VBUS_VBUS") (pintype "bidirectional"))
    )
  )
)
